# stm32_1.net
KiCad netlist of a schematic drawn in EasyEDA Pro
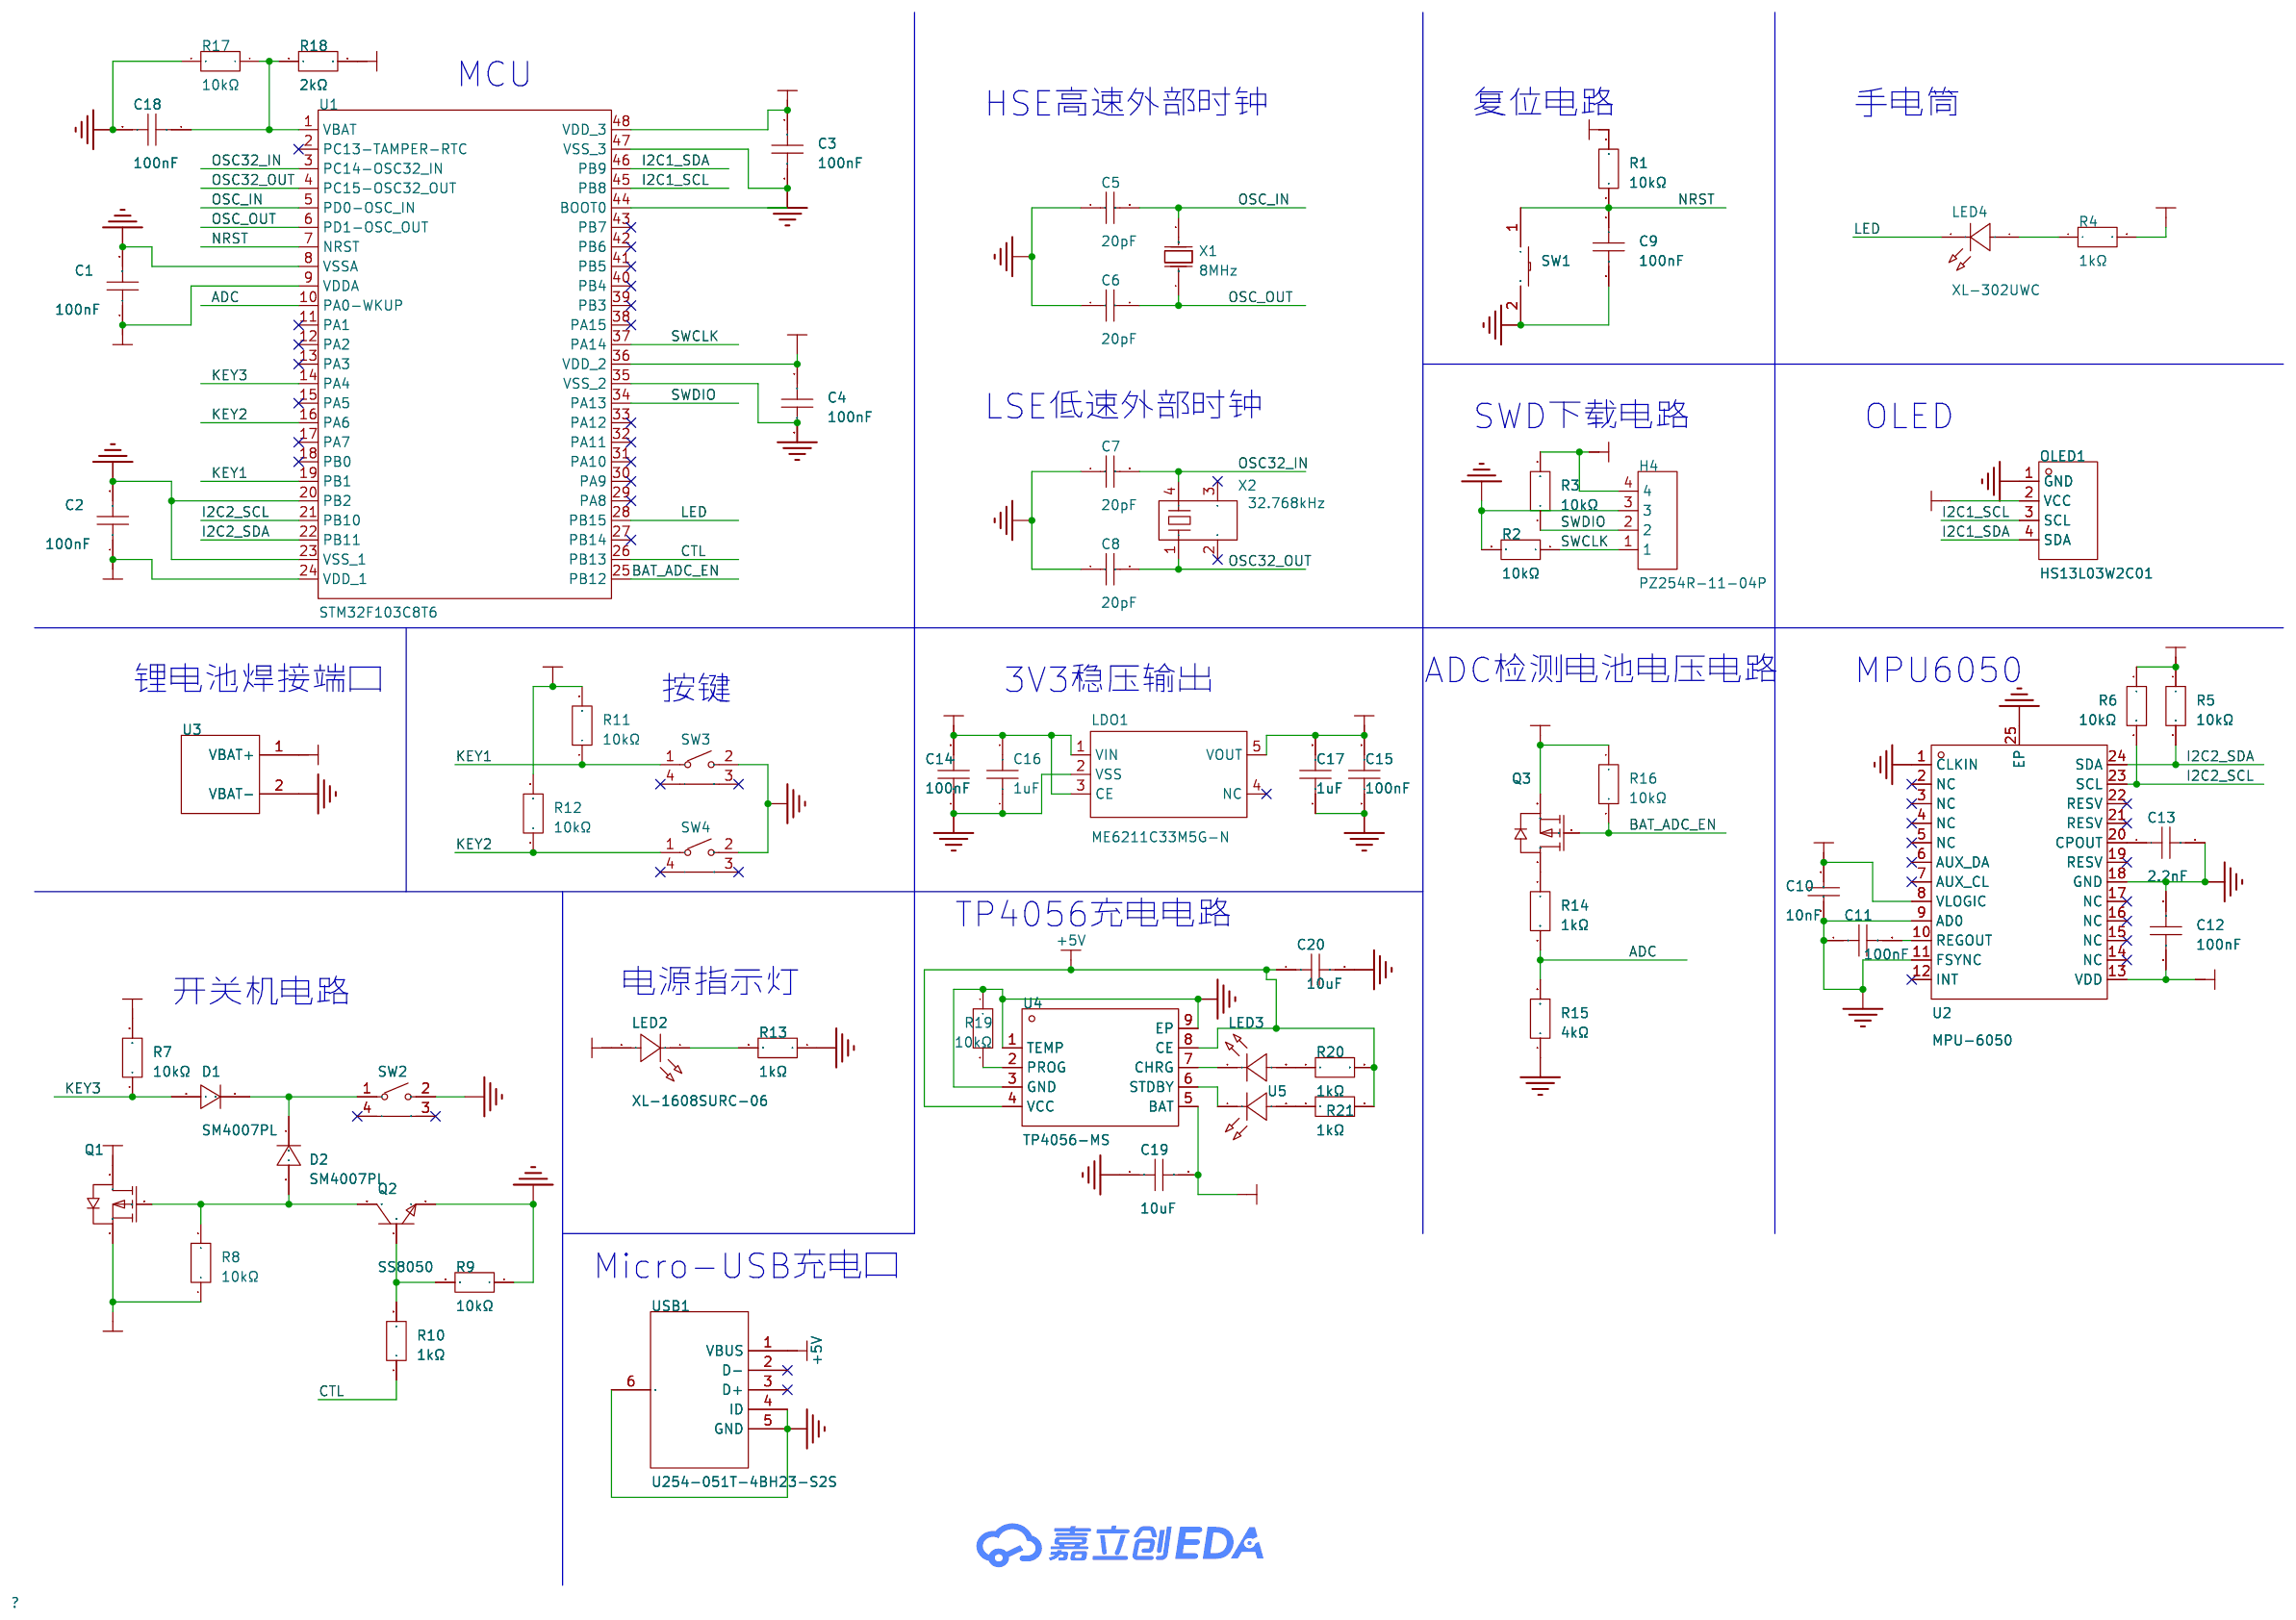
[diagram p0: schematic sheet]

(export (version "E")
  (design (tool "Eeschema 10.0.6"))
  (components
    (comp (ref "C1")
      (value "100nF")
      (footprint "easyedapro:C0603")
      (description "容值:100nF;精度:±10%;额定电压:50V;温度系数:X7R;")
      (fields
        (field (name "Manufacturer Part") "CC0603KRX7R9BB104")
        (field (name "Manufacturer") "YAGEO(国巨)")
      )
      (libsource (lib "easyedapro") (part "CC0603KRX7R9BB104"))
    )
    (comp (ref "C2")
      (value "100nF")
      (footprint "easyedapro:C0603")
      (description "容值:100nF;精度:±10%;额定电压:50V;温度系数:X7R;")
      (fields
        (field (name "Manufacturer Part") "CC0603KRX7R9BB104")
        (field (name "Manufacturer") "YAGEO(国巨)")
      )
      (libsource (lib "easyedapro") (part "CC0603KRX7R9BB104"))
    )
    (comp (ref "C3")
      (value "100nF")
      (footprint "easyedapro:C0603")
      (description "容值:100nF;精度:±10%;额定电压:50V;温度系数:X7R;")
      (fields
        (field (name "Manufacturer Part") "CC0603KRX7R9BB104")
        (field (name "Manufacturer") "YAGEO(国巨)")
      )
      (libsource (lib "easyedapro") (part "CC0603KRX7R9BB104"))
    )
    (comp (ref "C4")
      (value "100nF")
      (footprint "easyedapro:C0603")
      (description "容值:100nF;精度:±10%;额定电压:50V;温度系数:X7R;")
      (fields
        (field (name "Manufacturer Part") "CC0603KRX7R9BB104")
        (field (name "Manufacturer") "YAGEO(国巨)")
      )
      (libsource (lib "easyedapro") (part "CC0603KRX7R9BB104"))
    )
    (comp (ref "C5")
      (value "20pF")
      (footprint "easyedapro:C0603")
      (description "容值:20pF;精度:±5%;额定电压:50V;材质(温度系数):C0G;")
      (fields
        (field (name "Manufacturer Part") "CL10C200JB8NNNC")
        (field (name "Manufacturer") "SAMSUNG(三星)")
      )
      (libsource (lib "easyedapro") (part "CL10C200JB8NNNC"))
    )
    (comp (ref "C6")
      (value "20pF")
      (footprint "easyedapro:C0603")
      (description "容值:20pF;精度:±5%;额定电压:50V;材质(温度系数):C0G;")
      (fields
        (field (name "Manufacturer Part") "CL10C200JB8NNNC")
        (field (name "Manufacturer") "SAMSUNG(三星)")
      )
      (libsource (lib "easyedapro") (part "CL10C200JB8NNNC"))
    )
    (comp (ref "C7")
      (value "20pF")
      (footprint "easyedapro:C0603")
      (description "容值:20pF;精度:±5%;额定电压:50V;材质(温度系数):C0G;")
      (fields
        (field (name "Manufacturer Part") "CL10C200JB8NNNC")
        (field (name "Manufacturer") "SAMSUNG(三星)")
      )
      (libsource (lib "easyedapro") (part "CL10C200JB8NNNC"))
    )
    (comp (ref "C8")
      (value "20pF")
      (footprint "easyedapro:C0603")
      (description "容值:20pF;精度:±5%;额定电压:50V;材质(温度系数):C0G;")
      (fields
        (field (name "Manufacturer Part") "CL10C200JB8NNNC")
        (field (name "Manufacturer") "SAMSUNG(三星)")
      )
      (libsource (lib "easyedapro") (part "CL10C200JB8NNNC"))
    )
    (comp (ref "C9")
      (value "100nF")
      (footprint "easyedapro:C0603")
      (description "容值:100nF;精度:±10%;额定电压:50V;温度系数:X7R;")
      (fields
        (field (name "Manufacturer Part") "CC0603KRX7R9BB104")
        (field (name "Manufacturer") "YAGEO(国巨)")
      )
      (libsource (lib "easyedapro") (part "CC0603KRX7R9BB104"))
    )
    (comp (ref "C10")
      (value "10nF")
      (footprint "easyedapro:C0603")
      (description "容值:10nF;精度:±10%;额定电压:50V;材质(温度系数):X7R;")
      (fields
        (field (name "Manufacturer Part") "CC0603KRX7R9BB103")
        (field (name "Manufacturer") "YAGEO(国巨)")
      )
      (libsource (lib "easyedapro") (part "CC0603KRX7R9BB103"))
    )
    (comp (ref "C11")
      (value "100nF")
      (footprint "easyedapro:C0603")
      (description "容值:100nF;精度:±10%;额定电压:50V;温度系数:X7R;")
      (fields
        (field (name "Manufacturer Part") "CC0603KRX7R9BB104")
        (field (name "Manufacturer") "YAGEO(国巨)")
      )
      (libsource (lib "easyedapro") (part "CC0603KRX7R9BB104"))
    )
    (comp (ref "C12")
      (value "100nF")
      (footprint "easyedapro:C0603")
      (description "容值:100nF;精度:±10%;额定电压:50V;温度系数:X7R;")
      (fields
        (field (name "Manufacturer Part") "CC0603KRX7R9BB104")
        (field (name "Manufacturer") "YAGEO(国巨)")
      )
      (libsource (lib "easyedapro") (part "CC0603KRX7R9BB104"))
    )
    (comp (ref "C13")
      (value "2.2nF")
      (footprint "easyedapro:C0603")
      (description "容值:2.2nF;精度:±10%;额定电压:50V;温度系数:X7R;")
      (fields
        (field (name "Manufacturer Part") "FCC0603B222K500CT")
        (field (name "Manufacturer") "FOJAN(富捷)")
      )
      (libsource (lib "easyedapro") (part "FCC0603B222K500CT"))
    )
    (comp (ref "C14")
      (value "100nF")
      (footprint "easyedapro:C0603")
      (description "容值:100nF;精度:±10%;额定电压:50V;温度系数:X7R;")
      (fields
        (field (name "Manufacturer Part") "CC0603KRX7R9BB104")
        (field (name "Manufacturer") "YAGEO(国巨)")
      )
      (libsource (lib "easyedapro") (part "CC0603KRX7R9BB104"))
    )
    (comp (ref "C15")
      (value "100nF")
      (footprint "easyedapro:C0603")
      (description "容值:100nF;精度:±10%;额定电压:50V;温度系数:X7R;")
      (fields
        (field (name "Manufacturer Part") "CC0603KRX7R9BB104")
        (field (name "Manufacturer") "YAGEO(国巨)")
      )
      (libsource (lib "easyedapro") (part "CC0603KRX7R9BB104"))
    )
    (comp (ref "C16")
      (value "1uF")
      (footprint "easyedapro:C0603")
      (description "容值:1uF;精度:±10%;额定电压:50V;材质(温度系数):X5R;")
      (fields
        (field (name "Manufacturer Part") "CL10A105KB8NNNC")
        (field (name "Manufacturer") "SAMSUNG(三星)")
      )
      (libsource (lib "easyedapro") (part "CL10A105KB8NNNC"))
    )
    (comp (ref "C17")
      (value "1uF")
      (footprint "easyedapro:C0603")
      (description "容值:1uF;精度:±10%;额定电压:50V;材质(温度系数):X5R;")
      (fields
        (field (name "Manufacturer Part") "CL10A105KB8NNNC")
        (field (name "Manufacturer") "SAMSUNG(三星)")
      )
      (libsource (lib "easyedapro") (part "CL10A105KB8NNNC"))
    )
    (comp (ref "C18")
      (value "100nF")
      (footprint "easyedapro:C0603")
      (description "容值:100nF;精度:±10%;额定电压:50V;温度系数:X7R;")
      (fields
        (field (name "Manufacturer Part") "CC0603KRX7R9BB104")
        (field (name "Manufacturer") "YAGEO(国巨)")
      )
      (libsource (lib "easyedapro") (part "CC0603KRX7R9BB104"))
    )
    (comp (ref "C19")
      (value "10uF")
      (footprint "easyedapro:C0603")
      (description "容值:10uF;精度:±10%;额定电压:10V;材质(温度系数):X5R;")
      (fields
        (field (name "Manufacturer Part") "CL10A106KP8NNNC")
        (field (name "Manufacturer") "SAMSUNG(三星)")
      )
      (libsource (lib "easyedapro") (part "CL10A106KP8NNNC"))
    )
    (comp (ref "C20")
      (value "10uF")
      (footprint "easyedapro:C0603")
      (description "容值:10uF;精度:±10%;额定电压:10V;材质(温度系数):X5R;")
      (fields
        (field (name "Manufacturer Part") "CL10A106KP8NNNC")
        (field (name "Manufacturer") "SAMSUNG(三星)")
      )
      (libsource (lib "easyedapro") (part "CL10A106KP8NNNC"))
    )
    (comp (ref "D1")
      (value "SM4007PL")
      (footprint "easyedapro:SOD-123F_L2.8-W1.8-LS3.7-RD")
      (description "二极管配置:独立式;正向压降(Vf):1.1V@1A;直流反向耐压(Vr):1kV;整流电流:1A;")
      (fields (field (name "Manufacturer") "MDD(辰达半导体)"))
      (libsource (lib "easyedapro") (part "SM4007PL"))
    )
    (comp (ref "D2")
      (value "SM4007PL")
      (footprint "easyedapro:SOD-123F_L2.8-W1.8-LS3.7-RD")
      (description "二极管配置:独立式;正向压降(Vf):1.1V@1A;直流反向耐压(Vr):1kV;整流电流:1A;")
      (fields (field (name "Manufacturer") "MDD(辰达半导体)"))
      (libsource (lib "easyedapro") (part "SM4007PL"))
    )
    (comp (ref "H4")
      (value "PZ254R-11-04P")
      (footprint "easyedapro:HDR-TH_4P-P2.54-H-M-W10.4")
      (fields (field (name "Manufacturer") "XFCN(兴飞)"))
      (libsource (lib "easyedapro") (part "PZ254R-11-04P"))
    )
    (comp (ref "LDO1")
      (value "ME6211C33M5G-N")
      (footprint "easyedapro:SOT-23-5_L3.0-W1.7-P0.95-LS2.8-BL")
      (description "输出类型:固定;工作电压:6V;输出电压:3.3V;输出电流:500mA;电源纹波抑制比(PSRR):70dB@(1kHz)；62dB@(10kHz);输出极性:正极;")
      (fields (field (name "Manufacturer") "MICRONE(南京微盟)"))
      (libsource (lib "easyedapro") (part "ME6211C33M5G-N"))
    )
    (comp (ref "LED2")
      (value "XL-1608SURC-06")
      (footprint "easyedapro:LED0603-RD_RED")
      (fields (field (name "Manufacturer") "XINGLIGHT(成兴光)"))
      (libsource (lib "easyedapro") (part "XL-1608SURC-06"))
    )
    (comp (ref "LED3")
      (value "XL-1608SURC-06")
      (footprint "easyedapro:LED0603-RD_RED")
      (fields (field (name "Manufacturer") "XINGLIGHT(成兴光)"))
      (libsource (lib "easyedapro") (part "XL-1608SURC-06"))
    )
    (comp (ref "LED4")
      (value "XL-302UWC")
      (footprint "easyedapro:LED-TH_BD3.8-P2.54-FD_WHITE")
      (fields (field (name "Manufacturer") "XINGLIGHT(成兴光)"))
      (libsource (lib "easyedapro") (part "XL-302UWC"))
    )
    (comp (ref "OLED1")
      (value "HS13L03W2C01")
      (footprint "easyedapro:OLED-TH_L35.4-W33.5_HS13L03W2C01")
      (description "主控芯片:SH1106;接口类型:I2C;尺寸(inch):1.3;")
      (fields (field (name "Manufacturer") "HS(汉昇)"))
      (libsource (lib "easyedapro") (part "HS13L03W2C01"))
    )
    (comp (ref "Q1")
      (value "SI2301CDS-T1-GE3")
      (footprint "easyedapro:SOT-23-3_L3.0-W1.7-P0.95-LS2.9-BR")
      (fields (field (name "Manufacturer") "VISHAY(威世)"))
      (libsource (lib "easyedapro") (part "SI2301CDS-T1-GE3"))
    )
    (comp (ref "Q2")
      (value "SS8050")
      (footprint "easyedapro:SOT-23-3_L2.9-W1.3-P1.90-LS2.4-BR")
      (description "晶体管类型:NPN;集电极电流(Ic):1.5A;集射极击穿电压(Vceo):25V;耗散功率(Pd):300mW;直流电流增益(hFE):120@100mA,1.0V;")
      (fields (field (name "Manufacturer") "宏嘉诚"))
      (libsource (lib "easyedapro") (part "SS8050_C7420370"))
    )
    (comp (ref "Q3")
      (value "SI2301CDS-T1-GE3")
      (footprint "easyedapro:SOT-23-3_L3.0-W1.7-P0.95-LS2.9-BR")
      (fields (field (name "Manufacturer") "VISHAY(威世)"))
      (libsource (lib "easyedapro") (part "SI2301CDS-T1-GE3"))
    )
    (comp (ref "R1")
      (value "10kΩ")
      (footprint "easyedapro:R0603")
      (description "电阻类型:厚膜电阻;阻值:10kΩ;精度:±5%;功率:100mW;工作电压:75V;温度系数:±100ppm/°C;")
      (fields (field (name "Manufacturer Part") "FRC0603J103 TS") (field (name "Manufacturer") "FOJAN(富捷)"))
      (libsource (lib "easyedapro") (part "FRC0603J103TS"))
    )
    (comp (ref "R2")
      (value "10kΩ")
      (footprint "easyedapro:R0603")
      (description "电阻类型:厚膜电阻;阻值:10kΩ;精度:±5%;功率:100mW;工作电压:75V;温度系数:±100ppm/°C;")
      (fields (field (name "Manufacturer Part") "FRC0603J103 TS") (field (name "Manufacturer") "FOJAN(富捷)"))
      (libsource (lib "easyedapro") (part "FRC0603J103TS"))
    )
    (comp (ref "R3")
      (value "10kΩ")
      (footprint "easyedapro:R0603")
      (description "电阻类型:厚膜电阻;阻值:10kΩ;精度:±5%;功率:100mW;工作电压:75V;温度系数:±100ppm/°C;")
      (fields (field (name "Manufacturer Part") "FRC0603J103 TS") (field (name "Manufacturer") "FOJAN(富捷)"))
      (libsource (lib "easyedapro") (part "FRC0603J103TS"))
    )
    (comp (ref "R4")
      (value "1kΩ")
      (footprint "easyedapro:R0603")
      (description "电阻类型:厚膜电阻;阻值:1kΩ;精度:±1%;功率:100mW;最大工作电压:75V;温度系数:±100ppm/°C;")
      (fields (field (name "Manufacturer Part") "FRC0603F1001TS") (field (name "Manufacturer") "FOJAN(富捷)"))
      (libsource (lib "easyedapro") (part "FRC0603F1001TS"))
    )
    (comp (ref "R5")
      (value "10kΩ")
      (footprint "easyedapro:R0603")
      (description "电阻类型:厚膜电阻;阻值:10kΩ;精度:±5%;功率:100mW;工作电压:75V;温度系数:±100ppm/°C;")
      (fields (field (name "Manufacturer Part") "FRC0603J103 TS") (field (name "Manufacturer") "FOJAN(富捷)"))
      (libsource (lib "easyedapro") (part "FRC0603J103TS"))
    )
    (comp (ref "R6")
      (value "10kΩ")
      (footprint "easyedapro:R0603")
      (description "电阻类型:厚膜电阻;阻值:10kΩ;精度:±5%;功率:100mW;工作电压:75V;温度系数:±100ppm/°C;")
      (fields (field (name "Manufacturer Part") "FRC0603J103 TS") (field (name "Manufacturer") "FOJAN(富捷)"))
      (libsource (lib "easyedapro") (part "FRC0603J103TS"))
    )
    (comp (ref "R7")
      (value "10kΩ")
      (footprint "easyedapro:R0603")
      (description "电阻类型:厚膜电阻;阻值:10kΩ;精度:±5%;功率:100mW;工作电压:75V;温度系数:±100ppm/°C;")
      (fields (field (name "Manufacturer Part") "FRC0603J103 TS") (field (name "Manufacturer") "FOJAN(富捷)"))
      (libsource (lib "easyedapro") (part "FRC0603J103TS"))
    )
    (comp (ref "R8")
      (value "10kΩ")
      (footprint "easyedapro:R0603")
      (description "电阻类型:厚膜电阻;阻值:10kΩ;精度:±5%;功率:100mW;工作电压:75V;温度系数:±100ppm/°C;")
      (fields (field (name "Manufacturer Part") "FRC0603J103 TS") (field (name "Manufacturer") "FOJAN(富捷)"))
      (libsource (lib "easyedapro") (part "FRC0603J103TS"))
    )
    (comp (ref "R9")
      (value "10kΩ")
      (footprint "easyedapro:R0603")
      (description "电阻类型:厚膜电阻;阻值:10kΩ;精度:±5%;功率:100mW;工作电压:75V;温度系数:±100ppm/°C;")
      (fields (field (name "Manufacturer Part") "FRC0603J103 TS") (field (name "Manufacturer") "FOJAN(富捷)"))
      (libsource (lib "easyedapro") (part "FRC0603J103TS"))
    )
    (comp (ref "R10")
      (value "1kΩ")
      (footprint "easyedapro:R0603")
      (description "电阻类型:厚膜电阻;阻值:1kΩ;精度:±1%;功率:100mW;最大工作电压:75V;温度系数:±100ppm/°C;")
      (fields (field (name "Manufacturer Part") "FRC0603F1001TS") (field (name "Manufacturer") "FOJAN(富捷)"))
      (libsource (lib "easyedapro") (part "FRC0603F1001TS"))
    )
    (comp (ref "R11")
      (value "10kΩ")
      (footprint "easyedapro:R0603")
      (description "电阻类型:厚膜电阻;阻值:10kΩ;精度:±5%;功率:100mW;工作电压:75V;温度系数:±100ppm/°C;")
      (fields (field (name "Manufacturer Part") "FRC0603J103 TS") (field (name "Manufacturer") "FOJAN(富捷)"))
      (libsource (lib "easyedapro") (part "FRC0603J103TS"))
    )
    (comp (ref "R12")
      (value "10kΩ")
      (footprint "easyedapro:R0603")
      (description "电阻类型:厚膜电阻;阻值:10kΩ;精度:±5%;功率:100mW;工作电压:75V;温度系数:±100ppm/°C;")
      (fields (field (name "Manufacturer Part") "FRC0603J103 TS") (field (name "Manufacturer") "FOJAN(富捷)"))
      (libsource (lib "easyedapro") (part "FRC0603J103TS"))
    )
    (comp (ref "R13")
      (value "1kΩ")
      (footprint "easyedapro:R0603")
      (description "电阻类型:厚膜电阻;阻值:1kΩ;精度:±1%;功率:100mW;最大工作电压:75V;温度系数:±100ppm/°C;")
      (fields (field (name "Manufacturer Part") "FRC0603F1001TS") (field (name "Manufacturer") "FOJAN(富捷)"))
      (libsource (lib "easyedapro") (part "FRC0603F1001TS"))
    )
    (comp (ref "R14")
      (value "1kΩ")
      (footprint "easyedapro:R0603")
      (description "电阻类型:厚膜电阻;阻值:1kΩ;精度:±1%;功率:100mW;最大工作电压:75V;温度系数:±100ppm/°C;")
      (fields (field (name "Manufacturer Part") "FRC0603F1001TS") (field (name "Manufacturer") "FOJAN(富捷)"))
      (libsource (lib "easyedapro") (part "FRC0603F1001TS"))
    )
    (comp (ref "R15")
      (value "4kΩ")
      (footprint "easyedapro:R0603")
      (description "电阻类型:薄膜电阻;阻值:4kΩ;精度:±1%;")
      (fields (field (name "Manufacturer Part") "ARG03FTC4001N") (field (name "Manufacturer") "Viking(光颉)"))
      (libsource (lib "easyedapro") (part "ARG03FTC4001N"))
    )
    (comp (ref "R16")
      (value "10kΩ")
      (footprint "easyedapro:R0603")
      (description "电阻类型:厚膜电阻;阻值:10kΩ;精度:±5%;功率:100mW;工作电压:75V;温度系数:±100ppm/°C;")
      (fields (field (name "Manufacturer Part") "FRC0603J103 TS") (field (name "Manufacturer") "FOJAN(富捷)"))
      (libsource (lib "easyedapro") (part "FRC0603J103TS"))
    )
    (comp (ref "R17")
      (value "10kΩ")
      (footprint "easyedapro:R0603")
      (description "电阻类型:厚膜电阻;阻值:10kΩ;精度:±5%;功率:100mW;工作电压:75V;温度系数:±100ppm/°C;")
      (fields (field (name "Manufacturer Part") "FRC0603J103 TS") (field (name "Manufacturer") "FOJAN(富捷)"))
      (libsource (lib "easyedapro") (part "FRC0603J103TS"))
    )
    (comp (ref "R18")
      (value "2kΩ")
      (footprint "easyedapro:R0603")
      (description "电阻类型:厚膜电阻;阻值:2kΩ;精度:±5%;功率:100mW;最大工作电压:75V;温度系数:±100ppm/°C;")
      (fields (field (name "Manufacturer Part") "FRC0603J202 TS") (field (name "Manufacturer") "FOJAN(富捷)"))
      (libsource (lib "easyedapro") (part "FRC0603J202 TS"))
    )
    (comp (ref "R19")
      (value "10kΩ")
      (footprint "easyedapro:R0603")
      (description "电阻类型:厚膜电阻;阻值:10kΩ;精度:±5%;功率:100mW;工作电压:75V;温度系数:±100ppm/°C;")
      (fields (field (name "Manufacturer Part") "FRC0603J103 TS") (field (name "Manufacturer") "FOJAN(富捷)"))
      (libsource (lib "easyedapro") (part "FRC0603J103TS"))
    )
    (comp (ref "R20")
      (value "1kΩ")
      (footprint "easyedapro:R0603")
      (description "电阻类型:厚膜电阻;阻值:1kΩ;精度:±1%;功率:100mW;最大工作电压:75V;温度系数:±100ppm/°C;")
      (fields (field (name "Manufacturer Part") "FRC0603F1001TS") (field (name "Manufacturer") "FOJAN(富捷)"))
      (libsource (lib "easyedapro") (part "FRC0603F1001TS"))
    )
    (comp (ref "R21")
      (value "1kΩ")
      (footprint "easyedapro:R0603")
      (description "电阻类型:厚膜电阻;阻值:1kΩ;精度:±1%;功率:100mW;最大工作电压:75V;温度系数:±100ppm/°C;")
      (fields (field (name "Manufacturer Part") "FRC0603F1001TS") (field (name "Manufacturer") "FOJAN(富捷)"))
      (libsource (lib "easyedapro") (part "FRC0603F1001TS"))
    )
    (comp (ref "SW1")
      (value "TS-1101-C-W")
      (footprint "easyedapro:SW-SMD_L6.0-W3.3-LS8.0")
      (fields (field (name "Manufacturer") "XKB Connectivity(中国星坤)"))
      (libsource (lib "easyedapro") (part "TS-1101-C-W"))
    )
    (comp (ref "SW2")
      (value "GT-TC018A-H0375-L1")
      (footprint "easyedapro:SW-SMD_L4.7-W3.5-P3.35-EH")
      (fields (field (name "Manufacturer") "G-Switch(品赞)"))
      (libsource (lib "easyedapro") (part "GT-TC018A-H0375-L1"))
    )
    (comp (ref "SW3")
      (value "GT-TC018A-H0375-L1")
      (footprint "easyedapro:SW-SMD_L4.7-W3.5-P3.35-EH")
      (fields (field (name "Manufacturer") "G-Switch(品赞)"))
      (libsource (lib "easyedapro") (part "GT-TC018A-H0375-L1"))
    )
    (comp (ref "SW4")
      (value "GT-TC018A-H0375-L1")
      (footprint "easyedapro:SW-SMD_L4.7-W3.5-P3.35-EH")
      (fields (field (name "Manufacturer") "G-Switch(品赞)"))
      (libsource (lib "easyedapro") (part "GT-TC018A-H0375-L1"))
    )
    (comp (ref "U1")
      (value "STM32F103C8T6")
      (footprint "easyedapro:LQFP-48_L7.0-W7.0-P0.50-LS9.0-BL")
      (description "CPU内核:ARM-M3;CPU最大主频:72MHz;应用领域:-;")
      (fields (field (name "Manufacturer") "ST(意法半导体)"))
      (libsource (lib "easyedapro") (part "STM32F103C8T6"))
    )
    (comp (ref "U2")
      (value "MPU-6050")
      (footprint "easyedapro:QFN-24_L4.0-W4.0-P0.50-BL-EP2.7")
      (description "传感器类型:加速度计陀螺仪;")
      (fields (field (name "Manufacturer") "TDK InvenSense(应美盛)"))
      (libsource (lib "easyedapro") (part "MPU-6050_C24112"))
    )
    (comp (ref "U3") (value "~") (libsource (lib "easyedapro") (part "302530BAT")))
    (comp (ref "U4")
      (value "TP4056-MS")
      (footprint "easyedapro:SOP-8_L4.9-W3.9-P1.27-LS6.0-TL-EP")
      (description "电源电压:4.2V~9V;最大充电电流:1A;电池类型:锂离子/聚合物;电池节数:1;")
      (fields (field (name "Manufacturer") "MSKSEMI(美森科)"))
      (libsource (lib "easyedapro") (part "TP4056-MS"))
    )
    (comp (ref "U5")
      (value "XL-1608PGC-06")
      (footprint "easyedapro:LED0603-RD_GREEN")
      (fields (field (name "Manufacturer") "XINGLIGHT(成兴光)"))
      (libsource (lib "easyedapro") (part "XL-1608PGC-06"))
    )
    (comp (ref "USB1")
      (value "U254-051T-4BH23-S2S")
      (footprint "easyedapro:MICRO-USB-SMD_U254-051T-4BH23-S2S")
      (fields (field (name "Manufacturer") "XKB Connection(中国星坤)"))
      (libsource (lib "easyedapro") (part "U254-051T-4BH23-S2S_C482361"))
    )
    (comp (ref "X1")
      (value "8MHz")
      (footprint "easyedapro:CRYSTAL-SMD_L5.0-W3.2")
      (description "晶振类型:贴片晶振;频率:8MHz;常温频差:±10ppm;负载电容:20pF;频率稳定度:±20ppm;")
      (fields (field (name "Manufacturer Part") "X50328MSB2GI") (field (name "Manufacturer") "YXC(扬兴晶振)"))
      (libsource (lib "easyedapro") (part "X50328MSB2GI"))
    )
    (comp (ref "X2")
      (value "32.768kHz")
      (footprint "easyedapro:MC-306_4P-L8.0-W3.2-P5.5-BL")
      (description "晶振类型:贴片晶振;频率:32.768kHz;常温频差:±20ppm;负载电容:12.5pF;")
      (fields (field (name "Manufacturer Part") "Q13MC30610003") (field (name "Manufacturer") "EPSON(爱普生)"))
      (libsource (lib "easyedapro") (part "Q13MC3061000300"))
    )
  )
  (nets
    (net (code "1") (name "+5V") (class "Default")
      (node (ref "C20") (pin "1") (pinfunction "1_1") (pintype "unspecified"))
      (node (ref "R20") (pin "2") (pinfunction "2_2") (pintype "unspecified"))
      (node (ref "R21") (pin "2") (pinfunction "2_2") (pintype "unspecified"))
      (node (ref "U4") (pin "4") (pinfunction "VCC_4") (pintype "unspecified"))
      (node (ref "U4") (pin "8") (pinfunction "CE_8") (pintype "unspecified"))
      (node (ref "USB1") (pin "1") (pinfunction "VBUS_1") (pintype "input"))
    )
    (net (code "2") (name "/ADC") (class "Default")
      (node (ref "R14") (pin "2") (pinfunction "2_2") (pintype "unspecified"))
      (node (ref "R15") (pin "2") (pinfunction "2_2") (pintype "unspecified"))
      (node (ref "U1") (pin "10") (pinfunction "PA0-WKUP_10") (pintype "unspecified"))
    )
    (net (code "3") (name "/BAT_ADC_EN") (class "Default")
      (node (ref "Q3") (pin "1") (pinfunction "G_1") (pintype "unspecified"))
      (node (ref "R16") (pin "2") (pinfunction "2_2") (pintype "unspecified"))
      (node (ref "U1") (pin "25") (pinfunction "PB12_25") (pintype "unspecified"))
    )
    (net (code "4") (name "/CTL") (class "Default")
      (node (ref "R10") (pin "1") (pinfunction "1_1") (pintype "unspecified"))
      (node (ref "U1") (pin "26") (pinfunction "PB13_26") (pintype "unspecified"))
    )
    (net (code "5") (name "/I2C1_SCL") (class "Default")
      (node (ref "OLED1") (pin "3") (pinfunction "SCL_3") (pintype "unspecified"))
      (node (ref "U1") (pin "45") (pinfunction "PB8_45") (pintype "unspecified"))
    )
    (net (code "6") (name "/I2C1_SDA") (class "Default")
      (node (ref "OLED1") (pin "4") (pinfunction "SDA_4") (pintype "unspecified"))
      (node (ref "U1") (pin "46") (pinfunction "PB9_46") (pintype "unspecified"))
    )
    (net (code "7") (name "/I2C2_SCL") (class "Default")
      (node (ref "R6") (pin "2") (pinfunction "2_2") (pintype "unspecified"))
      (node (ref "U1") (pin "21") (pinfunction "PB10_21") (pintype "unspecified"))
      (node (ref "U2") (pin "23") (pinfunction "SCL_23") (pintype "unspecified"))
    )
    (net (code "8") (name "/I2C2_SDA") (class "Default")
      (node (ref "R5") (pin "2") (pinfunction "2_2") (pintype "unspecified"))
      (node (ref "U1") (pin "22") (pinfunction "PB11_22") (pintype "unspecified"))
      (node (ref "U2") (pin "24") (pinfunction "SDA_24") (pintype "unspecified"))
    )
    (net (code "9") (name "/KEY1") (class "Default")
      (node (ref "R11") (pin "1") (pinfunction "1_1") (pintype "unspecified"))
      (node (ref "SW3") (pin "1") (pinfunction "1_1") (pintype "unspecified"))
      (node (ref "U1") (pin "19") (pinfunction "PB1_19") (pintype "unspecified"))
    )
    (net (code "10") (name "/KEY2") (class "Default")
      (node (ref "R12") (pin "1") (pinfunction "1_1") (pintype "unspecified"))
      (node (ref "SW4") (pin "1") (pinfunction "1_1") (pintype "unspecified"))
      (node (ref "U1") (pin "16") (pinfunction "PA6_16") (pintype "unspecified"))
    )
    (net (code "11") (name "/KEY3") (class "Default")
      (node (ref "D1") (pin "2") (pinfunction "A_2") (pintype "unspecified"))
      (node (ref "R7") (pin "1") (pinfunction "1_1") (pintype "unspecified"))
      (node (ref "U1") (pin "14") (pinfunction "PA4_14") (pintype "unspecified"))
    )
    (net (code "12") (name "/LED") (class "Default")
      (node (ref "LED4") (pin "2") (pinfunction "K_2") (pintype "unspecified"))
      (node (ref "U1") (pin "28") (pinfunction "PB15_28") (pintype "unspecified"))
    )
    (net (code "13") (name "/NRST") (class "Default")
      (node (ref "C9") (pin "1") (pinfunction "1_1") (pintype "unspecified"))
      (node (ref "R1") (pin "1") (pinfunction "1_1") (pintype "unspecified"))
      (node (ref "SW1") (pin "1") (pinfunction "1_1") (pintype "unspecified"))
      (node (ref "U1") (pin "7") (pinfunction "NRST_7") (pintype "unspecified"))
    )
    (net (code "14") (name "/OSC32_IN") (class "Default")
      (node (ref "C7") (pin "2") (pinfunction "2_2") (pintype "input"))
      (node (ref "U1") (pin "3") (pinfunction "PC14-OSC32_IN_3") (pintype "unspecified"))
      (node (ref "X2") (pin "4") (pinfunction "4_4") (pintype "unspecified"))
    )
    (net (code "15") (name "/OSC32_OUT") (class "Default")
      (node (ref "C8") (pin "2") (pinfunction "2_2") (pintype "input"))
      (node (ref "U1") (pin "4") (pinfunction "PC15-OSC32_OUT_4") (pintype "unspecified"))
      (node (ref "X2") (pin "1") (pinfunction "1_1") (pintype "unspecified"))
    )
    (net (code "16") (name "/OSC_IN") (class "Default")
      (node (ref "C5") (pin "2") (pinfunction "2_2") (pintype "input"))
      (node (ref "U1") (pin "5") (pinfunction "PD0-OSC_IN_5") (pintype "unspecified"))
      (node (ref "X1") (pin "2") (pinfunction "OSC2_2") (pintype "input"))
    )
    (net (code "17") (name "/OSC_OUT") (class "Default")
      (node (ref "C6") (pin "2") (pinfunction "2_2") (pintype "input"))
      (node (ref "U1") (pin "6") (pinfunction "PD1-OSC_OUT_6") (pintype "unspecified"))
      (node (ref "X1") (pin "1") (pinfunction "OSC1_1") (pintype "input"))
    )
    (net (code "18") (name "/SWCLK") (class "Default")
      (node (ref "H4") (pin "1") (pinfunction "1_1") (pintype "unspecified"))
      (node (ref "R2") (pin "1") (pinfunction "1_1") (pintype "unspecified"))
      (node (ref "U1") (pin "37") (pinfunction "PA14_37") (pintype "unspecified"))
    )
    (net (code "19") (name "/SWDIO") (class "Default")
      (node (ref "H4") (pin "2") (pinfunction "2_2") (pintype "unspecified"))
      (node (ref "R3") (pin "1") (pinfunction "1_1") (pintype "unspecified"))
      (node (ref "U1") (pin "34") (pinfunction "PA13_34") (pintype "unspecified"))
    )
    (net (code "20") (name "3V3") (class "Default")
      (node (ref "C1") (pin "1") (pinfunction "1_1") (pintype "unspecified"))
      (node (ref "C10") (pin "2") (pinfunction "2_2") (pintype "input"))
      (node (ref "C12") (pin "1") (pinfunction "1_1") (pintype "unspecified"))
      (node (ref "C15") (pin "2") (pinfunction "2_2") (pintype "unspecified"))
      (node (ref "C17") (pin "2") (pinfunction "2_2") (pintype "unspecified"))
      (node (ref "C2") (pin "1") (pinfunction "1_1") (pintype "unspecified"))
      (node (ref "C3") (pin "1") (pinfunction "1_1") (pintype "unspecified"))
      (node (ref "C4") (pin "1") (pinfunction "1_1") (pintype "unspecified"))
      (node (ref "H4") (pin "4") (pinfunction "4_4") (pintype "unspecified"))
      (node (ref "LDO1") (pin "5") (pinfunction "VOUT_5") (pintype "unspecified"))
      (node (ref "LED2") (pin "2") (pinfunction "A_2") (pintype "unspecified"))
      (node (ref "OLED1") (pin "2") (pinfunction "VCC_2") (pintype "unspecified"))
      (node (ref "R1") (pin "2") (pinfunction "2_2") (pintype "unspecified"))
      (node (ref "R11") (pin "2") (pinfunction "2_2") (pintype "unspecified"))
      (node (ref "R12") (pin "2") (pinfunction "2_2") (pintype "unspecified"))
      (node (ref "R3") (pin "2") (pinfunction "2_2") (pintype "unspecified"))
      (node (ref "R4") (pin "2") (pinfunction "2_2") (pintype "unspecified"))
      (node (ref "R5") (pin "1") (pinfunction "1_1") (pintype "unspecified"))
      (node (ref "R6") (pin "1") (pinfunction "1_1") (pintype "unspecified"))
      (node (ref "R7") (pin "2") (pinfunction "2_2") (pintype "unspecified"))
      (node (ref "U1") (pin "24") (pinfunction "VDD_1_24") (pintype "unspecified"))
      (node (ref "U1") (pin "36") (pinfunction "VDD_2_36") (pintype "unspecified"))
      (node (ref "U1") (pin "48") (pinfunction "VDD_3_48") (pintype "unspecified"))
      (node (ref "U1") (pin "9") (pinfunction "VDDA_9") (pintype "unspecified"))
      (node (ref "U2") (pin "13") (pinfunction "VDD_13") (pintype "unspecified"))
      (node (ref "U2") (pin "8") (pinfunction "VLOGIC_8") (pintype "unspecified"))
    )
    (net (code "21") (name "GND") (class "Default")
      (node (ref "C1") (pin "2") (pinfunction "2_2") (pintype "unspecified"))
      (node (ref "C10") (pin "1") (pinfunction "1_1") (pintype "input"))
      (node (ref "C11") (pin "1") (pinfunction "1_1") (pintype "unspecified"))
      (node (ref "C12") (pin "2") (pinfunction "2_2") (pintype "unspecified"))
      (node (ref "C13") (pin "2") (pinfunction "2_2") (pintype "unspecified"))
      (node (ref "C14") (pin "1") (pinfunction "1_1") (pintype "unspecified"))
      (node (ref "C15") (pin "1") (pinfunction "1_1") (pintype "unspecified"))
      (node (ref "C16") (pin "1") (pinfunction "1_1") (pintype "unspecified"))
      (node (ref "C17") (pin "1") (pinfunction "1_1") (pintype "unspecified"))
      (node (ref "C18") (pin "2") (pinfunction "2_2") (pintype "unspecified"))
      (node (ref "C19") (pin "1") (pinfunction "1_1") (pintype "unspecified"))
      (node (ref "C2") (pin "2") (pinfunction "2_2") (pintype "unspecified"))
      (node (ref "C20") (pin "2") (pinfunction "2_2") (pintype "unspecified"))
      (node (ref "C3") (pin "2") (pinfunction "2_2") (pintype "unspecified"))
      (node (ref "C4") (pin "2") (pinfunction "2_2") (pintype "unspecified"))
      (node (ref "C5") (pin "1") (pinfunction "1_1") (pintype "input"))
      (node (ref "C6") (pin "1") (pinfunction "1_1") (pintype "input"))
      (node (ref "C7") (pin "1") (pinfunction "1_1") (pintype "input"))
      (node (ref "C8") (pin "1") (pinfunction "1_1") (pintype "input"))
      (node (ref "C9") (pin "2") (pinfunction "2_2") (pintype "unspecified"))
      (node (ref "H4") (pin "3") (pinfunction "3_3") (pintype "unspecified"))
      (node (ref "LDO1") (pin "2") (pinfunction "VSS_2") (pintype "unspecified"))
      (node (ref "OLED1") (pin "1") (pinfunction "GND_1") (pintype "unspecified"))
      (node (ref "Q2") (pin "2") (pinfunction "E_2") (pintype "input"))
      (node (ref "R13") (pin "1") (pinfunction "1_1") (pintype "unspecified"))
      (node (ref "R15") (pin "1") (pinfunction "1_1") (pintype "unspecified"))
      (node (ref "R17") (pin "2") (pinfunction "2_2") (pintype "unspecified"))
      (node (ref "R19") (pin "1") (pinfunction "1_1") (pintype "unspecified"))
      (node (ref "R2") (pin "2") (pinfunction "2_2") (pintype "unspecified"))
      (node (ref "R9") (pin "1") (pinfunction "1_1") (pintype "unspecified"))
      (node (ref "SW1") (pin "2") (pinfunction "2_2") (pintype "unspecified"))
      (node (ref "SW2") (pin "2") (pinfunction "2_2") (pintype "unspecified"))
      (node (ref "SW3") (pin "2") (pinfunction "2_2") (pintype "unspecified"))
      (node (ref "SW4") (pin "2") (pinfunction "2_2") (pintype "unspecified"))
      (node (ref "U1") (pin "20") (pinfunction "PB2_20") (pintype "unspecified"))
      (node (ref "U1") (pin "23") (pinfunction "VSS_1_23") (pintype "unspecified"))
      (node (ref "U1") (pin "35") (pinfunction "VSS_2_35") (pintype "unspecified"))
      (node (ref "U1") (pin "44") (pinfunction "BOOT0_44") (pintype "unspecified"))
      (node (ref "U1") (pin "47") (pinfunction "VSS_3_47") (pintype "unspecified"))
      (node (ref "U1") (pin "8") (pinfunction "VSSA_8") (pintype "unspecified"))
      (node (ref "U2") (pin "1") (pinfunction "CLKIN_1") (pintype "unspecified"))
      (node (ref "U2") (pin "11") (pinfunction "FSYNC_11") (pintype "unspecified"))
      (node (ref "U2") (pin "18") (pinfunction "GND_18") (pintype "unspecified"))
      (node (ref "U2") (pin "25") (pinfunction "EP_25") (pintype "unspecified"))
      (node (ref "U2") (pin "9") (pinfunction "AD0_9") (pintype "unspecified"))
      (node (ref "U3") (pin "2") (pinfunction "VBAT-_2") (pintype "input"))
      (node (ref "U4") (pin "1") (pinfunction "TEMP_1") (pintype "unspecified"))
      (node (ref "U4") (pin "3") (pinfunction "GND_3") (pintype "unspecified"))
      (node (ref "U4") (pin "9") (pinfunction "EP_9") (pintype "unspecified"))
      (node (ref "USB1") (pin "4") (pinfunction "ID_4") (pintype "input"))
      (node (ref "USB1") (pin "5") (pinfunction "GND_5") (pintype "input"))
      (node (ref "USB1") (pin "6") (pinfunction "EH_6") (pintype "input"))
    )
    (net (code "22") (name "Net-(D1-C)") (class "Default")
      (node (ref "D1") (pin "1") (pinfunction "C_1") (pintype "unspecified"))
      (node (ref "D2") (pin "1") (pinfunction "C_1") (pintype "unspecified"))
      (node (ref "SW2") (pin "1") (pinfunction "1_1") (pintype "unspecified"))
    )
    (net (code "23") (name "Net-(D2-A)") (class "Default")
      (node (ref "D2") (pin "2") (pinfunction "A_2") (pintype "unspecified"))
      (node (ref "Q1") (pin "1") (pinfunction "G_1") (pintype "unspecified"))
      (node (ref "Q2") (pin "3") (pinfunction "C_3") (pintype "input"))
      (node (ref "R8") (pin "2") (pinfunction "2_2") (pintype "unspecified"))
    )
    (net (code "24") (name "Net-(LED2-K)") (class "Default")
      (node (ref "LED2") (pin "1") (pinfunction "K_1") (pintype "unspecified"))
      (node (ref "R13") (pin "2") (pinfunction "2_2") (pintype "unspecified"))
    )
    (net (code "25") (name "Net-(LED3-A)") (class "Default")
      (node (ref "LED3") (pin "2") (pinfunction "A_2") (pintype "unspecified"))
      (node (ref "R20") (pin "1") (pinfunction "1_1") (pintype "unspecified"))
    )
    (net (code "26") (name "Net-(LED3-K)") (class "Default")
      (node (ref "LED3") (pin "1") (pinfunction "K_1") (pintype "unspecified"))
      (node (ref "U4") (pin "7") (pinfunction "CHRG_7") (pintype "unspecified"))
    )
    (net (code "27") (name "Net-(LED4-A)") (class "Default")
      (node (ref "LED4") (pin "1") (pinfunction "A_1") (pintype "unspecified"))
      (node (ref "R4") (pin "1") (pinfunction "1_1") (pintype "unspecified"))
    )
    (net (code "28") (name "Net-(Q2-B)") (class "Default")
      (node (ref "Q2") (pin "1") (pinfunction "B_1") (pintype "input"))
      (node (ref "R10") (pin "2") (pinfunction "2_2") (pintype "unspecified"))
      (node (ref "R9") (pin "2") (pinfunction "2_2") (pintype "unspecified"))
    )
    (net (code "29") (name "Net-(Q3-D)") (class "Default")
      (node (ref "Q3") (pin "3") (pinfunction "D_3") (pintype "unspecified"))
      (node (ref "R14") (pin "1") (pinfunction "1_1") (pintype "unspecified"))
    )
    (net (code "30") (name "Net-(U1-VBAT)") (class "Default")
      (node (ref "C18") (pin "1") (pinfunction "1_1") (pintype "unspecified"))
      (node (ref "R17") (pin "1") (pinfunction "1_1") (pintype "unspecified"))
      (node (ref "R18") (pin "1") (pinfunction "1_1") (pintype "unspecified"))
      (node (ref "U1") (pin "1") (pinfunction "VBAT_1") (pintype "unspecified"))
    )
    (net (code "31") (name "Net-(U2-CPOUT)") (class "Default")
      (node (ref "C13") (pin "1") (pinfunction "1_1") (pintype "unspecified"))
      (node (ref "U2") (pin "20") (pinfunction "CPOUT_20") (pintype "unspecified"))
    )
    (net (code "32") (name "Net-(U2-REGOUT)") (class "Default")
      (node (ref "C11") (pin "2") (pinfunction "2_2") (pintype "unspecified"))
      (node (ref "U2") (pin "10") (pinfunction "REGOUT_10") (pintype "unspecified"))
    )
    (net (code "33") (name "Net-(U4-PROG)") (class "Default")
      (node (ref "R19") (pin "2") (pinfunction "2_2") (pintype "unspecified"))
      (node (ref "U4") (pin "2") (pinfunction "PROG_2") (pintype "unspecified"))
    )
    (net (code "34") (name "Net-(U4-STDBY)") (class "Default")
      (node (ref "U4") (pin "6") (pinfunction "STDBY_6") (pintype "unspecified"))
      (node (ref "U5") (pin "1") (pinfunction "K_1") (pintype "unspecified"))
    )
    (net (code "35") (name "Net-(U5-A)") (class "Default")
      (node (ref "R21") (pin "1") (pinfunction "1_1") (pintype "unspecified"))
      (node (ref "U5") (pin "2") (pinfunction "A_2") (pintype "unspecified"))
    )
    (net (code "36") (name "VBAT") (class "Default")
      (node (ref "C14") (pin "2") (pinfunction "2_2") (pintype "unspecified"))
      (node (ref "C16") (pin "2") (pinfunction "2_2") (pintype "unspecified"))
      (node (ref "LDO1") (pin "1") (pinfunction "VIN_1") (pintype "unspecified"))
      (node (ref "LDO1") (pin "3") (pinfunction "CE_3") (pintype "unspecified"))
      (node (ref "Q1") (pin "3") (pinfunction "D_3") (pintype "unspecified"))
    )
    (net (code "37") (name "VBAT+") (class "Default")
      (node (ref "C19") (pin "2") (pinfunction "2_2") (pintype "unspecified"))
      (node (ref "Q1") (pin "2") (pinfunction "S_2") (pintype "unspecified"))
      (node (ref "Q3") (pin "2") (pinfunction "S_2") (pintype "unspecified"))
      (node (ref "R16") (pin "1") (pinfunction "1_1") (pintype "unspecified"))
      (node (ref "R18") (pin "2") (pinfunction "2_2") (pintype "unspecified"))
      (node (ref "R8") (pin "1") (pinfunction "1_1") (pintype "unspecified"))
      (node (ref "U3") (pin "1") (pinfunction "VBAT+_1") (pintype "input"))
      (node (ref "U4") (pin "5") (pinfunction "BAT_5") (pintype "unspecified"))
    )
    (net (code "38") (name "unconnected-(LDO1-NC-Pad4)") (class "Default")
      (node (ref "LDO1") (pin "4") (pinfunction "NC_4") (pintype "unspecified+no_connect"))
    )
    (net (code "39") (name "unconnected-(SW2-Pad3)") (class "Default")
      (node (ref "SW2") (pin "3") (pinfunction "3_3") (pintype "unspecified+no_connect"))
    )
    (net (code "40") (name "unconnected-(SW2-Pad4)") (class "Default")
      (node (ref "SW2") (pin "4") (pinfunction "4_4") (pintype "unspecified+no_connect"))
    )
    (net (code "41") (name "unconnected-(SW3-Pad3)") (class "Default")
      (node (ref "SW3") (pin "3") (pinfunction "3_3") (pintype "unspecified+no_connect"))
    )
    (net (code "42") (name "unconnected-(SW3-Pad4)") (class "Default")
      (node (ref "SW3") (pin "4") (pinfunction "4_4") (pintype "unspecified+no_connect"))
    )
    (net (code "43") (name "unconnected-(SW4-Pad3)") (class "Default")
      (node (ref "SW4") (pin "3") (pinfunction "3_3") (pintype "unspecified+no_connect"))
    )
    (net (code "44") (name "unconnected-(SW4-Pad4)") (class "Default")
      (node (ref "SW4") (pin "4") (pinfunction "4_4") (pintype "unspecified+no_connect"))
    )
    (net (code "45") (name "unconnected-(U1-PA1-Pad11)") (class "Default")
      (node (ref "U1") (pin "11") (pinfunction "PA1_11") (pintype "unspecified+no_connect"))
    )
    (net (code "46") (name "unconnected-(U1-PA2-Pad12)") (class "Default")
      (node (ref "U1") (pin "12") (pinfunction "PA2_12") (pintype "unspecified+no_connect"))
    )
    (net (code "47") (name "unconnected-(U1-PA3-Pad13)") (class "Default")
      (node (ref "U1") (pin "13") (pinfunction "PA3_13") (pintype "unspecified+no_connect"))
    )
    (net (code "48") (name "unconnected-(U1-PA5-Pad15)") (class "Default")
      (node (ref "U1") (pin "15") (pinfunction "PA5_15") (pintype "unspecified+no_connect"))
    )
    (net (code "49") (name "unconnected-(U1-PA7-Pad17)") (class "Default")
      (node (ref "U1") (pin "17") (pinfunction "PA7_17") (pintype "unspecified+no_connect"))
    )
    (net (code "50") (name "unconnected-(U1-PA8-Pad29)") (class "Default")
      (node (ref "U1") (pin "29") (pinfunction "PA8_29") (pintype "unspecified+no_connect"))
    )
    (net (code "51") (name "unconnected-(U1-PA9-Pad30)") (class "Default")
      (node (ref "U1") (pin "30") (pinfunction "PA9_30") (pintype "unspecified+no_connect"))
    )
    (net (code "52") (name "unconnected-(U1-PA10-Pad31)") (class "Default")
      (node (ref "U1") (pin "31") (pinfunction "PA10_31") (pintype "unspecified+no_connect"))
    )
    (net (code "53") (name "unconnected-(U1-PA11-Pad32)") (class "Default")
      (node (ref "U1") (pin "32") (pinfunction "PA11_32") (pintype "unspecified+no_connect"))
    )
    (net (code "54") (name "unconnected-(U1-PA12-Pad33)") (class "Default")
      (node (ref "U1") (pin "33") (pinfunction "PA12_33") (pintype "unspecified+no_connect"))
    )
    (net (code "55") (name "unconnected-(U1-PA15-Pad38)") (class "Default")
      (node (ref "U1") (pin "38") (pinfunction "PA15_38") (pintype "unspecified+no_connect"))
    )
    (net (code "56") (name "unconnected-(U1-PB0-Pad18)") (class "Default")
      (node (ref "U1") (pin "18") (pinfunction "PB0_18") (pintype "unspecified+no_connect"))
    )
    (net (code "57") (name "unconnected-(U1-PB3-Pad39)") (class "Default")
      (node (ref "U1") (pin "39") (pinfunction "PB3_39") (pintype "unspecified+no_connect"))
    )
    (net (code "58") (name "unconnected-(U1-PB4-Pad40)") (class "Default")
      (node (ref "U1") (pin "40") (pinfunction "PB4_40") (pintype "unspecified+no_connect"))
    )
    (net (code "59") (name "unconnected-(U1-PB5-Pad41)") (class "Default")
      (node (ref "U1") (pin "41") (pinfunction "PB5_41") (pintype "unspecified+no_connect"))
    )
    (net (code "60") (name "unconnected-(U1-PB6-Pad42)") (class "Default")
      (node (ref "U1") (pin "42") (pinfunction "PB6_42") (pintype "unspecified+no_connect"))
    )
    (net (code "61") (name "unconnected-(U1-PB7-Pad43)") (class "Default")
      (node (ref "U1") (pin "43") (pinfunction "PB7_43") (pintype "unspecified+no_connect"))
    )
    (net (code "62") (name "unconnected-(U1-PB14-Pad27)") (class "Default")
      (node (ref "U1") (pin "27") (pinfunction "PB14_27") (pintype "unspecified+no_connect"))
    )
    (net (code "63") (name "unconnected-(U1-PC13-TAMPER-RTC-Pad2)") (class "Default")
      (node (ref "U1") (pin "2") (pinfunction "PC13-TAMPER-RTC_2") (pintype "unspecified+no_connect"))
    )
    (net (code "64") (name "unconnected-(U2-AUX_CL-Pad7)") (class "Default")
      (node (ref "U2") (pin "7") (pinfunction "AUX_CL_7") (pintype "unspecified+no_connect"))
    )
    (net (code "65") (name "unconnected-(U2-AUX_DA-Pad6)") (class "Default")
      (node (ref "U2") (pin "6") (pinfunction "AUX_DA_6") (pintype "unspecified+no_connect"))
    )
    (net (code "66") (name "unconnected-(U2-INT-Pad12)") (class "Default")
      (node (ref "U2") (pin "12") (pinfunction "INT_12") (pintype "unspecified+no_connect"))
    )
    (net (code "67") (name "unconnected-(U2-NC-Pad2)") (class "Default")
      (node (ref "U2") (pin "2") (pinfunction "NC_2") (pintype "unspecified+no_connect"))
    )
    (net (code "68") (name "unconnected-(U2-NC-Pad3)") (class "Default")
      (node (ref "U2") (pin "3") (pinfunction "NC_3") (pintype "unspecified+no_connect"))
    )
    (net (code "69") (name "unconnected-(U2-NC-Pad4)") (class "Default")
      (node (ref "U2") (pin "4") (pinfunction "NC_4") (pintype "unspecified+no_connect"))
    )
    (net (code "70") (name "unconnected-(U2-NC-Pad5)") (class "Default")
      (node (ref "U2") (pin "5") (pinfunction "NC_5") (pintype "unspecified+no_connect"))
    )
    (net (code "71") (name "unconnected-(U2-NC-Pad14)") (class "Default")
      (node (ref "U2") (pin "14") (pinfunction "NC_14") (pintype "unspecified+no_connect"))
    )
    (net (code "72") (name "unconnected-(U2-NC-Pad15)") (class "Default")
      (node (ref "U2") (pin "15") (pinfunction "NC_15") (pintype "unspecified+no_connect"))
    )
    (net (code "73") (name "unconnected-(U2-NC-Pad16)") (class "Default")
      (node (ref "U2") (pin "16") (pinfunction "NC_16") (pintype "unspecified+no_connect"))
    )
    (net (code "74") (name "unconnected-(U2-NC-Pad17)") (class "Default")
      (node (ref "U2") (pin "17") (pinfunction "NC_17") (pintype "unspecified+no_connect"))
    )
    (net (code "75") (name "unconnected-(U2-RESV-Pad19)") (class "Default")
      (node (ref "U2") (pin "19") (pinfunction "RESV_19") (pintype "unspecified+no_connect"))
    )
    (net (code "76") (name "unconnected-(U2-RESV-Pad21)") (class "Default")
      (node (ref "U2") (pin "21") (pinfunction "RESV_21") (pintype "unspecified+no_connect"))
    )
    (net (code "77") (name "unconnected-(U2-RESV-Pad22)") (class "Default")
      (node (ref "U2") (pin "22") (pinfunction "RESV_22") (pintype "unspecified+no_connect"))
    )
    (net (code "78") (name "unconnected-(USB1-D+-Pad3)") (class "Default")
      (node (ref "USB1") (pin "3") (pinfunction "D+_3") (pintype "input+no_connect"))
    )
    (net (code "79") (name "unconnected-(USB1-D--Pad2)") (class "Default")
      (node (ref "USB1") (pin "2") (pinfunction "D-_2") (pintype "input+no_connect"))
    )
    (net (code "80") (name "unconnected-(X2-Pad2)") (class "Default")
      (node (ref "X2") (pin "2") (pinfunction "2_2") (pintype "unspecified+no_connect"))
    )
    (net (code "81") (name "unconnected-(X2-Pad3)") (class "Default")
      (node (ref "X2") (pin "3") (pinfunction "3_3") (pintype "unspecified+no_connect"))
    )
  )
)
